# DAC_DifferenceAmp_backup.net
KiCad netlist of a schematic drawn in Altium Designer
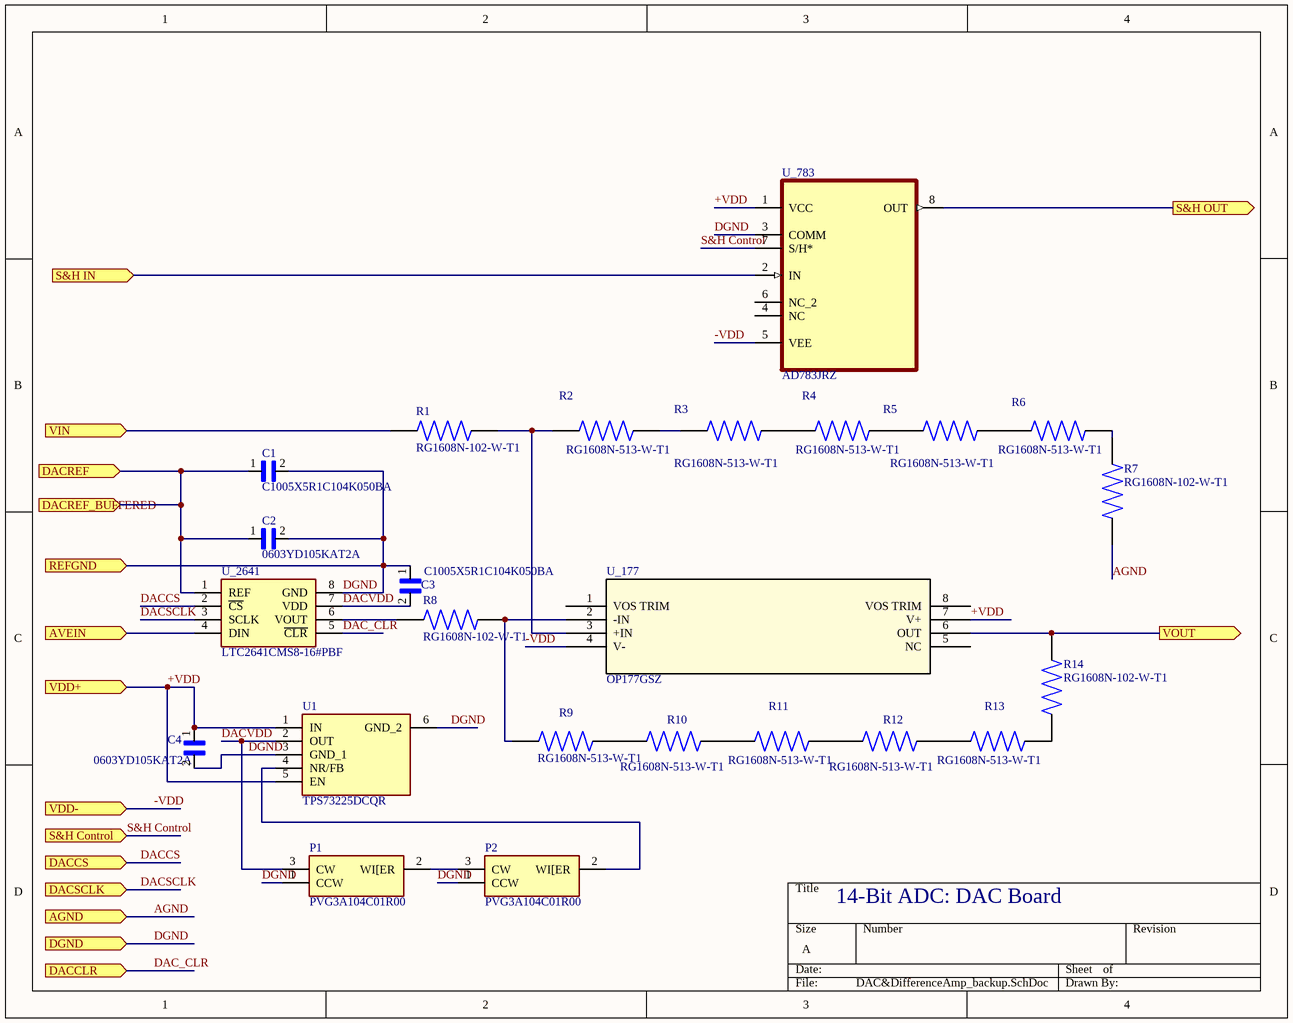
[diagram p0: DAC&DifferenceAmp_backup.SchDoc]

(export (version "E")
  (design (tool "Eeschema 10.0.6"))
  (components
    (comp (ref "C1")
      (value "C1005X5R1C104K050BA")
      (footprint "CAPC1005X55N")
      (description "CERAMIC CAPACITOR, 0.1UF, 16V, X5R, 10%, 0402")
      (libsource (lib "") (part "C1005X5R1C104K050BA_1"))
    )
    (comp (ref "C2")
      (value "0603YD105KAT2A")
      (footprint "CAPC1608X90N")
      (description "1ÂµF Â±10% 16V Ceramic Capacitor X5R 0603 (1608 Metric)")
      (fields (field (name "MF") "AVX"))
      (libsource (lib "0603YD105KAT2A") (part "0603YD105KAT2A"))
    )
    (comp (ref "C3")
      (value "C1005X5R1C104K050BA")
      (footprint "CAPC1005X55N")
      (description "CERAMIC CAPACITOR, 0.1UF, 16V, X5R, 10%, 0402")
      (libsource (lib "C1005X5R1C104K050BA") (part "C1005X5R1C104K050BA"))
    )
    (comp (ref "C4")
      (value "0603YD105KAT2A")
      (footprint "CAPC1608X90N")
      (description "1ÂµF Â±10% 16V Ceramic Capacitor X5R 0603 (1608 Metric)")
      (fields (field (name "MF") "AVX"))
      (libsource (lib "") (part "0603YD105KAT2A_1"))
    )
    (comp (ref "P1")
      (value "PVG3A104C01R00")
      (footprint "SamacSys:PVG3A104C01R00")
      (description "Variable Resistor")
      (fields (field (name "MOUSER2 PART NUMBER") "81-PVG3A104C01R00"))
      (libsource (lib "*") (part "PVG3A104C01R00"))
    )
    (comp (ref "P2")
      (value "PVG3A104C01R00")
      (footprint "SamacSys:PVG3A104C01R00")
      (description "Variable Resistor")
      (fields (field (name "MOUSER2 PART NUMBER") "81-PVG3A104C01R00"))
      (libsource (lib "*") (part "PVG3A104C01R00"))
    )
    (comp (ref "R1")
      (value "RG1608N-102-W-T1")
      (footprint "RESC1608X50N")
      (description "RES SMD 1K OHM 0.05% 1/10W 0603")
      (libsource (lib "RG1608N-102-W-T1") (part "RG1608N-102-W-T1"))
    )
    (comp (ref "R2")
      (value "RG1608N-513-W-T1")
      (footprint "RESC1608X50N")
      (libsource (lib "RG1608N-513-W-T1") (part "RG1608N-513-W-T1"))
    )
    (comp (ref "R3")
      (value "RG1608N-513-W-T1")
      (footprint "RESC1608X50N")
      (libsource (lib "RG1608N-513-W-T1") (part "RG1608N-513-W-T1"))
    )
    (comp (ref "R4")
      (value "RG1608N-513-W-T1")
      (footprint "RESC1608X50N")
      (libsource (lib "RG1608N-513-W-T1") (part "RG1608N-513-W-T1"))
    )
    (comp (ref "R5")
      (value "RG1608N-513-W-T1")
      (footprint "RESC1608X50N")
      (libsource (lib "RG1608N-513-W-T1") (part "RG1608N-513-W-T1"))
    )
    (comp (ref "R6")
      (value "RG1608N-513-W-T1")
      (footprint "RESC1608X50N")
      (libsource (lib "RG1608N-513-W-T1") (part "RG1608N-513-W-T1"))
    )
    (comp (ref "R7")
      (value "RG1608N-102-W-T1")
      (footprint "RESC1608X50N")
      (description "RES SMD 1K OHM 0.05% 1/10W 0603")
      (libsource (lib "RG1608N-102-W-T1") (part "RG1608N-102-W-T1"))
    )
    (comp (ref "R8")
      (value "RG1608N-102-W-T1")
      (footprint "RESC1608X50N")
      (description "RES SMD 1K OHM 0.05% 1/10W 0603")
      (libsource (lib "RG1608N-102-W-T1") (part "RG1608N-102-W-T1"))
    )
    (comp (ref "R9")
      (value "RG1608N-513-W-T1")
      (footprint "RESC1608X50N")
      (libsource (lib "RG1608N-513-W-T1") (part "RG1608N-513-W-T1"))
    )
    (comp (ref "R10")
      (value "RG1608N-513-W-T1")
      (footprint "RESC1608X50N")
      (libsource (lib "RG1608N-513-W-T1") (part "RG1608N-513-W-T1"))
    )
    (comp (ref "R11")
      (value "RG1608N-513-W-T1")
      (footprint "RESC1608X50N")
      (libsource (lib "RG1608N-513-W-T1") (part "RG1608N-513-W-T1"))
    )
    (comp (ref "R12")
      (value "RG1608N-513-W-T1")
      (footprint "RESC1608X50N")
      (libsource (lib "RG1608N-513-W-T1") (part "RG1608N-513-W-T1"))
    )
    (comp (ref "R13")
      (value "RG1608N-513-W-T1")
      (footprint "RESC1608X50N")
      (libsource (lib "RG1608N-513-W-T1") (part "RG1608N-513-W-T1"))
    )
    (comp (ref "R14")
      (value "RG1608N-102-W-T1")
      (footprint "RESC1608X50N")
      (description "RES SMD 1K OHM 0.05% 1/10W 0603")
      (libsource (lib "RG1608N-102-W-T1") (part "RG1608N-102-W-T1"))
    )
    (comp (ref "U1")
      (value "TPS73225DCQR")
      (footprint "SamacSys:SOT127P706X180-6N")
      (description "Integrated Circuit")
      (libsource (lib "*") (part "TPS73225DCQR"))
    )
    (comp (ref "U_177")
      (value "OP177GSZ")
      (footprint "R_8_ADI")
      (description "No Description Available")
      (fields (field (name "COPYRIGHT") "Copyright (C) 2021 Accelerated Designs. All rights reserved"))
      (libsource (lib "OP177GSZ") (part "OP177GSZ"))
    )
    (comp (ref "U_783")
      (value "AD783JRZ")
      (footprint "SOIC127P600X272-8N")
      (description "Sample and Hold Amplifier 1 Circuit 8-SOIC")
      (fields (field (name "MF") "Analog Devices"))
      (libsource (lib "AD783JRZ") (part "AD783JRZ"))
    )
    (comp (ref "U_2641")
      (value "LTC2641CMS8-16#PBF")
      (footprint "SamacSys:SOP65P490X110-8N")
      (description "Integrated Circuit")
      (fields (field (name "MOUSER PART NUMBER") "584-C2641CMS8-16PBF"))
      (libsource (lib "*") (part "LTC2641CMS8-16#PBF"))
    )
  )
  (nets
    (net (code "1") (name "/+VDD") (class "Default")
      (node (ref "C4") (pin "1") (pinfunction "1_1") (pintype "passive"))
      (node (ref "U1") (pin "1") (pinfunction "IN_1") (pintype "passive"))
      (node (ref "U1") (pin "5") (pinfunction "EN_5") (pintype "passive"))
      (node (ref "U_177") (pin "7") (pinfunction "V+_7") (pintype "power_in"))
      (node (ref "U_783") (pin "1") (pinfunction "VCC_1") (pintype "power_in"))
    )
    (net (code "2") (name "/-VDD") (class "Default")
      (node (ref "U_177") (pin "4") (pinfunction "V-_4") (pintype "power_in"))
      (node (ref "U_783") (pin "5") (pinfunction "VEE_5") (pintype "power_in"))
    )
    (net (code "3") (name "/AGND") (class "Default")
      (node (ref "R7") (pin "1") (pinfunction "1_1") (pintype "passive"))
    )
    (net (code "4") (name "/AVEIN") (class "Default")
      (node (ref "U_2641") (pin "4") (pinfunction "DIN_4") (pintype "passive"))
    )
    (net (code "5") (name "/DACCS") (class "Default")
      (node (ref "U_2641") (pin "2") (pinfunction "~{CS}_2") (pintype "passive"))
    )
    (net (code "6") (name "/DACREF") (class "Default")
      (node (ref "C1") (pin "1") (pinfunction "1_1") (pintype "passive"))
      (node (ref "C2") (pin "1") (pinfunction "1_1") (pintype "passive"))
      (node (ref "U_2641") (pin "1") (pinfunction "REF_1") (pintype "passive"))
    )
    (net (code "7") (name "/DACSCLK") (class "Default")
      (node (ref "U_2641") (pin "3") (pinfunction "SCLK_3") (pintype "passive"))
    )
    (net (code "8") (name "/DACVDD") (class "Default")
      (node (ref "C3") (pin "2") (pinfunction "2_2") (pintype "passive"))
      (node (ref "P1") (pin "3") (pinfunction "CW_3") (pintype "passive"))
      (node (ref "U1") (pin "2") (pinfunction "OUT_2") (pintype "passive"))
      (node (ref "U_2641") (pin "7") (pinfunction "VDD_7") (pintype "passive"))
    )
    (net (code "9") (name "/DAC_CLR") (class "Default")
      (node (ref "U_2641") (pin "5") (pinfunction "~{CLR}_5") (pintype "passive"))
    )
    (net (code "10") (name "/DGND") (class "Default")
      (node (ref "C1") (pin "2") (pinfunction "2_2") (pintype "passive"))
      (node (ref "C2") (pin "2") (pinfunction "2_2") (pintype "passive"))
      (node (ref "C3") (pin "1") (pinfunction "1_1") (pintype "passive"))
      (node (ref "C4") (pin "2") (pinfunction "2_2") (pintype "passive"))
      (node (ref "P1") (pin "1") (pinfunction "CCW_1") (pintype "passive"))
      (node (ref "P2") (pin "1") (pinfunction "CCW_1") (pintype "passive"))
      (node (ref "U1") (pin "3") (pinfunction "GND_1_3") (pintype "passive"))
      (node (ref "U1") (pin "6") (pinfunction "GND_2_6") (pintype "passive"))
      (node (ref "U_2641") (pin "8") (pinfunction "GND_8") (pintype "passive"))
      (node (ref "U_783") (pin "3") (pinfunction "COMM_3") (pintype "passive"))
    )
    (net (code "11") (name "/S&H Control") (class "Default")
      (node (ref "U_783") (pin "7") (pinfunction "S/H*_7") (pintype "passive"))
    )
    (net (code "12") (name "/S&H IN") (class "Default")
      (node (ref "U_783") (pin "2") (pinfunction "IN_2") (pintype "input"))
    )
    (net (code "13") (name "/S&H OUT") (class "Default")
      (node (ref "U_783") (pin "8") (pinfunction "OUT_8") (pintype "output"))
    )
    (net (code "14") (name "/VIN") (class "Default")
      (node (ref "R1") (pin "1") (pinfunction "1_1") (pintype "passive"))
    )
    (net (code "15") (name "/VOUT") (class "Default")
      (node (ref "R14") (pin "2") (pinfunction "2_2") (pintype "passive"))
      (node (ref "U_177") (pin "6") (pinfunction "OUT_6") (pintype "passive"))
    )
    (net (code "16") (name "Net-(P1-WI[ER)") (class "Default")
      (node (ref "P1") (pin "2") (pinfunction "WI[ER_2") (pintype "passive"))
      (node (ref "P2") (pin "3") (pinfunction "CW_3") (pintype "passive"))
    )
    (net (code "17") (name "Net-(P2-WI[ER)") (class "Default")
      (node (ref "P2") (pin "2") (pinfunction "WI[ER_2") (pintype "passive"))
      (node (ref "U1") (pin "4") (pinfunction "NR/FB_4") (pintype "passive"))
    )
    (net (code "18") (name "Net-(R2-Pad2)") (class "Default")
      (node (ref "R2") (pin "2") (pinfunction "2_2") (pintype "passive"))
      (node (ref "R3") (pin "1") (pinfunction "1_1") (pintype "passive"))
    )
    (net (code "19") (name "Net-(R3-Pad2)") (class "Default")
      (node (ref "R3") (pin "2") (pinfunction "2_2") (pintype "passive"))
      (node (ref "R4") (pin "1") (pinfunction "1_1") (pintype "passive"))
    )
    (net (code "20") (name "Net-(R4-Pad2)") (class "Default")
      (node (ref "R4") (pin "2") (pinfunction "2_2") (pintype "passive"))
      (node (ref "R5") (pin "1") (pinfunction "1_1") (pintype "passive"))
    )
    (net (code "21") (name "Net-(R5-Pad2)") (class "Default")
      (node (ref "R5") (pin "2") (pinfunction "2_2") (pintype "passive"))
      (node (ref "R6") (pin "1") (pinfunction "1_1") (pintype "passive"))
    )
    (net (code "22") (name "Net-(R6-Pad2)") (class "Default")
      (node (ref "R6") (pin "2") (pinfunction "2_2") (pintype "passive"))
      (node (ref "R7") (pin "2") (pinfunction "2_2") (pintype "passive"))
    )
    (net (code "23") (name "Net-(R10-Pad1)") (class "Default")
      (node (ref "R10") (pin "1") (pinfunction "1_1") (pintype "passive"))
      (node (ref "R9") (pin "2") (pinfunction "2_2") (pintype "passive"))
    )
    (net (code "24") (name "Net-(R10-Pad2)") (class "Default")
      (node (ref "R10") (pin "2") (pinfunction "2_2") (pintype "passive"))
      (node (ref "R11") (pin "1") (pinfunction "1_1") (pintype "passive"))
    )
    (net (code "25") (name "Net-(R11-Pad2)") (class "Default")
      (node (ref "R11") (pin "2") (pinfunction "2_2") (pintype "passive"))
      (node (ref "R12") (pin "1") (pinfunction "1_1") (pintype "passive"))
    )
    (net (code "26") (name "Net-(R12-Pad2)") (class "Default")
      (node (ref "R12") (pin "2") (pinfunction "2_2") (pintype "passive"))
      (node (ref "R13") (pin "1") (pinfunction "1_1") (pintype "passive"))
    )
    (net (code "27") (name "Net-(R13-Pad2)") (class "Default")
      (node (ref "R13") (pin "2") (pinfunction "2_2") (pintype "passive"))
      (node (ref "R14") (pin "1") (pinfunction "1_1") (pintype "passive"))
    )
    (net (code "28") (name "Net-(U_177-+IN)") (class "Default")
      (node (ref "R1") (pin "2") (pinfunction "2_2") (pintype "passive"))
      (node (ref "R2") (pin "1") (pinfunction "1_1") (pintype "passive"))
      (node (ref "U_177") (pin "3") (pinfunction "+IN_3") (pintype "passive"))
    )
    (net (code "29") (name "Net-(U_177--IN)") (class "Default")
      (node (ref "R8") (pin "2") (pinfunction "2_2") (pintype "passive"))
      (node (ref "R9") (pin "1") (pinfunction "1_1") (pintype "passive"))
      (node (ref "U_177") (pin "2") (pinfunction "-IN_2") (pintype "passive"))
    )
    (net (code "30") (name "Net-(U_2641-VOUT)") (class "Default")
      (node (ref "R8") (pin "1") (pinfunction "1_1") (pintype "passive"))
      (node (ref "U_2641") (pin "6") (pinfunction "VOUT_6") (pintype "passive"))
    )
    (net (code "31") (name "unconnected-(U_177-NC-Pad5)") (class "Default")
      (node (ref "U_177") (pin "5") (pinfunction "NC_5") (pintype "passive"))
    )
    (net (code "32") (name "unconnected-(U_177-VOS_TRIM-Pad1)") (class "Default")
      (node (ref "U_177") (pin "1") (pinfunction "VOS_TRIM_1") (pintype "passive"))
    )
    (net (code "33") (name "unconnected-(U_177-VOS_TRIM-Pad8)") (class "Default")
      (node (ref "U_177") (pin "8") (pinfunction "VOS_TRIM_8") (pintype "power_in"))
    )
    (net (code "34") (name "unconnected-(U_783-NC-Pad4)") (class "Default")
      (node (ref "U_783") (pin "4") (pinfunction "NC_4") (pintype "passive"))
    )
    (net (code "35") (name "unconnected-(U_783-NC_2-Pad6)") (class "Default")
      (node (ref "U_783") (pin "6") (pinfunction "NC_2_6") (pintype "passive"))
    )
  )
)
